# config-bank7.net
KiCad netlist of a schematic drawn in Altium Designer
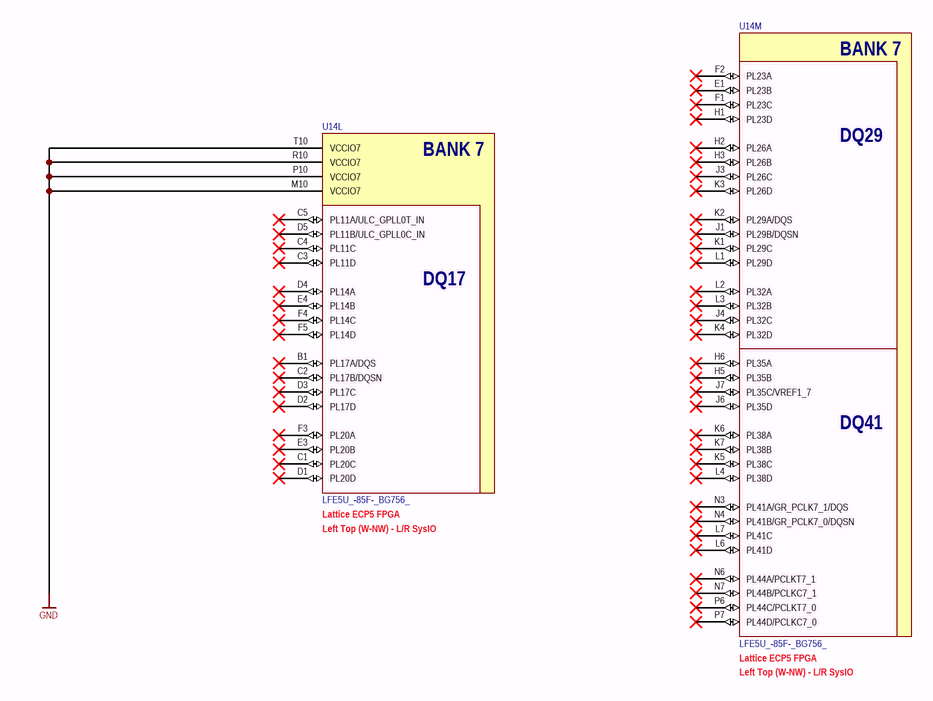
[diagram p0: config-bank7.SchDoc]

(export (version "E")
  (design (tool "Eeschema 10.0.6"))
  (components
    (comp (ref "U14")
      (value "LFE5U_-85F-_BG756_")
      (footprint "lattice:caBGA756")
      (description "ECP5 FPGA, 85k LUT, 756-caBGA")
      (fields (field (name "MANUFACTURER") "Lattice Semiconductor"))
      (libsource (lib "lattice") (part "LFE5U_-85F-_BG756_"))
    )
  )
  (nets
    (net (code "1") (name "GND") (class "Default")
      (node (ref "U14") (pin "M10") (pinfunction "VCCIO7_M10") (pintype "power_in"))
      (node (ref "U14") (pin "P10") (pinfunction "VCCIO7_P10") (pintype "power_in"))
      (node (ref "U14") (pin "R10") (pinfunction "VCCIO7_R10") (pintype "power_in"))
      (node (ref "U14") (pin "T10") (pinfunction "VCCIO7_T10") (pintype "power_in"))
    )
    (net (code "2") (name "unconnected-(U14L-PL11A{slash}ULC_GPLL0T_IN-PadC5)") (class "Default")
      (node (ref "U14") (pin "C5") (pinfunction "PL11A/ULC_GPLL0T_IN_C5") (pintype "bidirectional+no_connect"))
    )
    (net (code "3") (name "unconnected-(U14L-PL11B{slash}ULC_GPLL0C_IN-PadD5)") (class "Default")
      (node (ref "U14") (pin "D5") (pinfunction "PL11B/ULC_GPLL0C_IN_D5") (pintype "bidirectional+no_connect"))
    )
    (net (code "4") (name "unconnected-(U14L-PL11C-PadC4)") (class "Default")
      (node (ref "U14") (pin "C4") (pinfunction "PL11C_C4") (pintype "bidirectional+no_connect"))
    )
    (net (code "5") (name "unconnected-(U14L-PL11D-PadC3)") (class "Default")
      (node (ref "U14") (pin "C3") (pinfunction "PL11D_C3") (pintype "bidirectional+no_connect"))
    )
    (net (code "6") (name "unconnected-(U14L-PL14A-PadD4)") (class "Default")
      (node (ref "U14") (pin "D4") (pinfunction "PL14A_D4") (pintype "bidirectional+no_connect"))
    )
    (net (code "7") (name "unconnected-(U14L-PL14B-PadE4)") (class "Default")
      (node (ref "U14") (pin "E4") (pinfunction "PL14B_E4") (pintype "bidirectional+no_connect"))
    )
    (net (code "8") (name "unconnected-(U14L-PL14C-PadF4)") (class "Default")
      (node (ref "U14") (pin "F4") (pinfunction "PL14C_F4") (pintype "bidirectional+no_connect"))
    )
    (net (code "9") (name "unconnected-(U14L-PL14D-PadF5)") (class "Default")
      (node (ref "U14") (pin "F5") (pinfunction "PL14D_F5") (pintype "bidirectional+no_connect"))
    )
    (net (code "10") (name "unconnected-(U14L-PL17A{slash}DQS-PadB1)") (class "Default")
      (node (ref "U14") (pin "B1") (pinfunction "PL17A/DQS_B1") (pintype "bidirectional+no_connect"))
    )
    (net (code "11") (name "unconnected-(U14L-PL17B{slash}DQSN-PadC2)") (class "Default")
      (node (ref "U14") (pin "C2") (pinfunction "PL17B/DQSN_C2") (pintype "bidirectional+no_connect"))
    )
    (net (code "12") (name "unconnected-(U14L-PL17C-PadD3)") (class "Default")
      (node (ref "U14") (pin "D3") (pinfunction "PL17C_D3") (pintype "bidirectional+no_connect"))
    )
    (net (code "13") (name "unconnected-(U14L-PL17D-PadD2)") (class "Default")
      (node (ref "U14") (pin "D2") (pinfunction "PL17D_D2") (pintype "bidirectional+no_connect"))
    )
    (net (code "14") (name "unconnected-(U14L-PL20A-PadF3)") (class "Default")
      (node (ref "U14") (pin "F3") (pinfunction "PL20A_F3") (pintype "bidirectional+no_connect"))
    )
    (net (code "15") (name "unconnected-(U14L-PL20B-PadE3)") (class "Default")
      (node (ref "U14") (pin "E3") (pinfunction "PL20B_E3") (pintype "bidirectional+no_connect"))
    )
    (net (code "16") (name "unconnected-(U14L-PL20C-PadC1)") (class "Default")
      (node (ref "U14") (pin "C1") (pinfunction "PL20C_C1") (pintype "bidirectional+no_connect"))
    )
    (net (code "17") (name "unconnected-(U14L-PL20D-PadD1)") (class "Default")
      (node (ref "U14") (pin "D1") (pinfunction "PL20D_D1") (pintype "bidirectional+no_connect"))
    )
    (net (code "18") (name "unconnected-(U14M-PL23A-PadF2)") (class "Default")
      (node (ref "U14") (pin "F2") (pinfunction "PL23A_F2") (pintype "bidirectional+no_connect"))
    )
    (net (code "19") (name "unconnected-(U14M-PL23B-PadE1)") (class "Default")
      (node (ref "U14") (pin "E1") (pinfunction "PL23B_E1") (pintype "bidirectional+no_connect"))
    )
    (net (code "20") (name "unconnected-(U14M-PL23C-PadF1)") (class "Default")
      (node (ref "U14") (pin "F1") (pinfunction "PL23C_F1") (pintype "bidirectional+no_connect"))
    )
    (net (code "21") (name "unconnected-(U14M-PL23D-PadH1)") (class "Default")
      (node (ref "U14") (pin "H1") (pinfunction "PL23D_H1") (pintype "bidirectional+no_connect"))
    )
    (net (code "22") (name "unconnected-(U14M-PL26A-PadH2)") (class "Default")
      (node (ref "U14") (pin "H2") (pinfunction "PL26A_H2") (pintype "bidirectional+no_connect"))
    )
    (net (code "23") (name "unconnected-(U14M-PL26B-PadH3)") (class "Default")
      (node (ref "U14") (pin "H3") (pinfunction "PL26B_H3") (pintype "bidirectional+no_connect"))
    )
    (net (code "24") (name "unconnected-(U14M-PL26C-PadJ3)") (class "Default")
      (node (ref "U14") (pin "J3") (pinfunction "PL26C_J3") (pintype "bidirectional+no_connect"))
    )
    (net (code "25") (name "unconnected-(U14M-PL26D-PadK3)") (class "Default")
      (node (ref "U14") (pin "K3") (pinfunction "PL26D_K3") (pintype "bidirectional+no_connect"))
    )
    (net (code "26") (name "unconnected-(U14M-PL29A{slash}DQS-PadK2)") (class "Default")
      (node (ref "U14") (pin "K2") (pinfunction "PL29A/DQS_K2") (pintype "bidirectional+no_connect"))
    )
    (net (code "27") (name "unconnected-(U14M-PL29B{slash}DQSN-PadJ1)") (class "Default")
      (node (ref "U14") (pin "J1") (pinfunction "PL29B/DQSN_J1") (pintype "bidirectional+no_connect"))
    )
    (net (code "28") (name "unconnected-(U14M-PL29C-PadK1)") (class "Default")
      (node (ref "U14") (pin "K1") (pinfunction "PL29C_K1") (pintype "bidirectional+no_connect"))
    )
    (net (code "29") (name "unconnected-(U14M-PL29D-PadL1)") (class "Default")
      (node (ref "U14") (pin "L1") (pinfunction "PL29D_L1") (pintype "bidirectional+no_connect"))
    )
    (net (code "30") (name "unconnected-(U14M-PL32A-PadL2)") (class "Default")
      (node (ref "U14") (pin "L2") (pinfunction "PL32A_L2") (pintype "bidirectional+no_connect"))
    )
    (net (code "31") (name "unconnected-(U14M-PL32B-PadL3)") (class "Default")
      (node (ref "U14") (pin "L3") (pinfunction "PL32B_L3") (pintype "bidirectional+no_connect"))
    )
    (net (code "32") (name "unconnected-(U14M-PL32C-PadJ4)") (class "Default")
      (node (ref "U14") (pin "J4") (pinfunction "PL32C_J4") (pintype "bidirectional+no_connect"))
    )
    (net (code "33") (name "unconnected-(U14M-PL32D-PadK4)") (class "Default")
      (node (ref "U14") (pin "K4") (pinfunction "PL32D_K4") (pintype "bidirectional+no_connect"))
    )
    (net (code "34") (name "unconnected-(U14M-PL35A-PadH6)") (class "Default")
      (node (ref "U14") (pin "H6") (pinfunction "PL35A_H6") (pintype "bidirectional+no_connect"))
    )
    (net (code "35") (name "unconnected-(U14M-PL35B-PadH5)") (class "Default")
      (node (ref "U14") (pin "H5") (pinfunction "PL35B_H5") (pintype "bidirectional+no_connect"))
    )
    (net (code "36") (name "unconnected-(U14M-PL35C{slash}VREF1_7-PadJ7)") (class "Default")
      (node (ref "U14") (pin "J7") (pinfunction "PL35C/VREF1_7_J7") (pintype "bidirectional+no_connect"))
    )
    (net (code "37") (name "unconnected-(U14M-PL35D-PadJ6)") (class "Default")
      (node (ref "U14") (pin "J6") (pinfunction "PL35D_J6") (pintype "bidirectional+no_connect"))
    )
    (net (code "38") (name "unconnected-(U14M-PL38A-PadK6)") (class "Default")
      (node (ref "U14") (pin "K6") (pinfunction "PL38A_K6") (pintype "bidirectional+no_connect"))
    )
    (net (code "39") (name "unconnected-(U14M-PL38B-PadK7)") (class "Default")
      (node (ref "U14") (pin "K7") (pinfunction "PL38B_K7") (pintype "bidirectional+no_connect"))
    )
    (net (code "40") (name "unconnected-(U14M-PL38C-PadK5)") (class "Default")
      (node (ref "U14") (pin "K5") (pinfunction "PL38C_K5") (pintype "bidirectional+no_connect"))
    )
    (net (code "41") (name "unconnected-(U14M-PL38D-PadL4)") (class "Default")
      (node (ref "U14") (pin "L4") (pinfunction "PL38D_L4") (pintype "bidirectional+no_connect"))
    )
    (net (code "42") (name "unconnected-(U14M-PL41A{slash}GR_PCLK7_1{slash}DQS-PadN3)") (class "Default")
      (node (ref "U14") (pin "N3") (pinfunction "PL41A/GR_PCLK7_1/DQS_N3") (pintype "bidirectional+no_connect"))
    )
    (net (code "43") (name "unconnected-(U14M-PL41B{slash}GR_PCLK7_0{slash}DQSN-PadN4)") (class "Default")
      (node (ref "U14") (pin "N4") (pinfunction "PL41B/GR_PCLK7_0/DQSN_N4") (pintype "bidirectional+no_connect"))
    )
    (net (code "44") (name "unconnected-(U14M-PL41C-PadL7)") (class "Default")
      (node (ref "U14") (pin "L7") (pinfunction "PL41C_L7") (pintype "bidirectional+no_connect"))
    )
    (net (code "45") (name "unconnected-(U14M-PL41D-PadL6)") (class "Default")
      (node (ref "U14") (pin "L6") (pinfunction "PL41D_L6") (pintype "bidirectional+no_connect"))
    )
    (net (code "46") (name "unconnected-(U14M-PL44A{slash}PCLKT7_1-PadN6)") (class "Default")
      (node (ref "U14") (pin "N6") (pinfunction "PL44A/PCLKT7_1_N6") (pintype "bidirectional+no_connect"))
    )
    (net (code "47") (name "unconnected-(U14M-PL44B{slash}PCLKC7_1-PadN7)") (class "Default")
      (node (ref "U14") (pin "N7") (pinfunction "PL44B/PCLKC7_1_N7") (pintype "bidirectional+no_connect"))
    )
    (net (code "48") (name "unconnected-(U14M-PL44C{slash}PCLKT7_0-PadP6)") (class "Default")
      (node (ref "U14") (pin "P6") (pinfunction "PL44C/PCLKT7_0_P6") (pintype "bidirectional+no_connect"))
    )
    (net (code "49") (name "unconnected-(U14M-PL44D{slash}PCLKC7_0-PadP7)") (class "Default")
      (node (ref "U14") (pin "P7") (pinfunction "PL44D/PCLKC7_0_P7") (pintype "bidirectional+no_connect"))
    )
  )
)
